# ATMEGA8A.net
KiCad netlist of a schematic drawn in Altium Designer
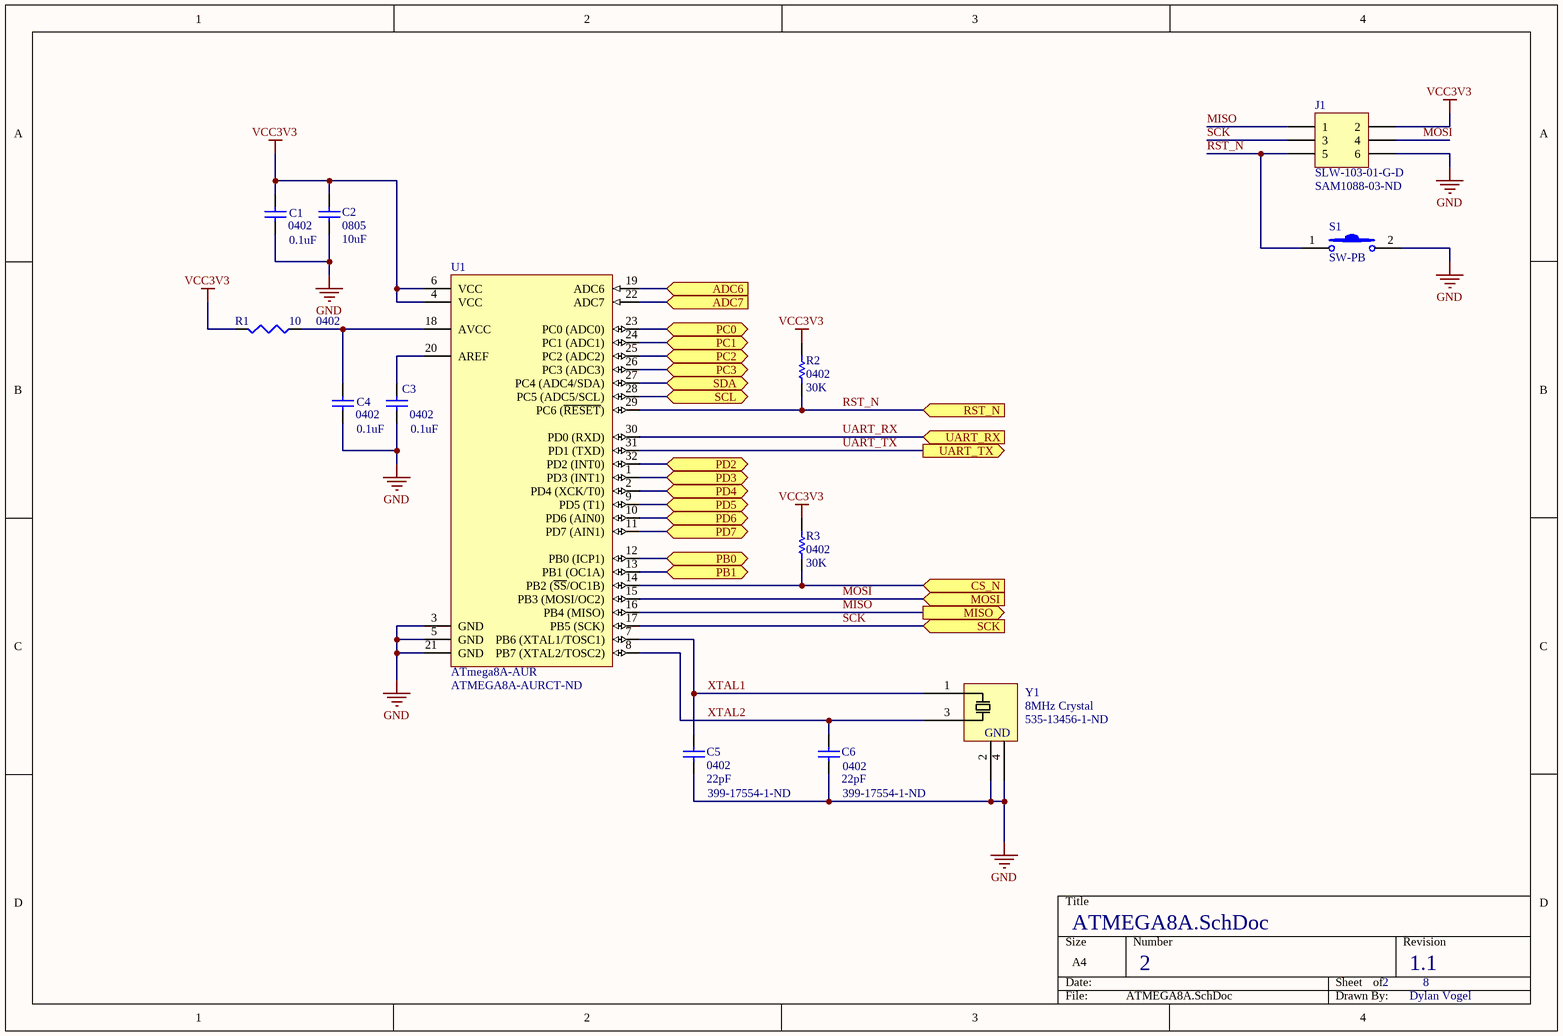
[diagram p0: ATMEGA8A.SchDoc]

(export (version "E")
  (design (tool "Eeschema 10.0.6"))
  (components
    (comp (ref "C1")
      (value "0402")
      (footprint "CAP0402R")
      (description "Capacitor (Semiconductor SIM Model)")
      (fields
        (field (name "ALTIUM_VALUE") "0.1uF")
        (field (name "MANUFACTURER") "Murata")
        (field (name "MANUFACTURER PART NUMBER") "GCM155R71C104KA55J")
        (field (name "PUBLISHER") "Altium Limited")
      )
      (libsource (lib "Miscellaneous Devices") (part "Cap Semi"))
    )
    (comp (ref "C2")
      (value "0805")
      (footprint "CAP0805R")
      (description "Capacitor")
      (fields
        (field (name "ALTIUM_VALUE") "10uF")
        (field (name "MANUFACTURER") "TDK")
        (field (name "MANUFACTURER PART NUMBER") "CGA4J1X7R0J106K125AC")
        (field (name "PUBLISHER") "Altium Limited")
      )
      (libsource (lib "Miscellaneous Devices") (part "Cap"))
    )
    (comp (ref "C3")
      (value "0402")
      (footprint "CAP0402R")
      (description "Capacitor (Semiconductor SIM Model)")
      (fields
        (field (name "ALTIUM_VALUE") "0.1uF")
        (field (name "MANUFACTURER") "Murata")
        (field (name "MANUFACTURER PART NUMBER") "GCM155R71C104KA55J")
        (field (name "PUBLISHER") "Altium Limited")
      )
      (libsource (lib "Miscellaneous Devices") (part "Cap Semi"))
    )
    (comp (ref "C4")
      (value "0402")
      (footprint "CAP0402R")
      (description "Capacitor (Semiconductor SIM Model)")
      (fields
        (field (name "ALTIUM_VALUE") "0.1uF")
        (field (name "MANUFACTURER") "Murata")
        (field (name "MANUFACTURER PART NUMBER") "GCM155R71C104KA55J")
        (field (name "PUBLISHER") "Altium Limited")
      )
      (libsource (lib "Miscellaneous Devices") (part "Cap Semi"))
    )
    (comp (ref "C5")
      (value "0402")
      (footprint "CAP0402R")
      (description "Capacitor")
      (fields
        (field (name "ALTIUM_VALUE") "22pF")
        (field (name "SUPPLIER PART NUMBER 1") "399-17554-1-ND")
        (field (name "MANUFACTURER") "KEMET")
        (field (name "MANUFACTURER PART NUMBER") "C0402C220K4RAC7867")
        (field (name "PUBLISHER") "Altium Limited")
      )
      (libsource (lib "Miscellaneous Devices") (part "Cap"))
    )
    (comp (ref "C6")
      (value "0402")
      (footprint "CAP0402R")
      (description "Capacitor")
      (fields
        (field (name "ALTIUM_VALUE") "22pF")
        (field (name "SUPPLIER PART NUMBER 1") "399-17554-1-ND")
        (field (name "MANUFACTURER") "KEMET")
        (field (name "MANUFACTURER PART NUMBER") "C0402C220K4RAC7867")
        (field (name "PUBLISHER") "Altium Limited")
      )
      (libsource (lib "Miscellaneous Devices") (part "Cap"))
    )
    (comp (ref "J1")
      (value "SLW-103-01-G-D")
      (footprint "SLW-103-01-X-D")
      (fields (field (name "SUPPLIER PART NUMBER 1") "SAM1088-03-ND"))
      (libsource (lib "heron-general") (part "SLW-103-01-G-D"))
    )
    (comp (ref "R1")
      (value "0402")
      (footprint "RES0402R")
      (description "Resistor")
      (fields (field (name "ALTIUM_VALUE") "10") (field (name "PUBLISHER") "Altium Limited"))
      (libsource (lib "Miscellaneous Devices") (part "Res3"))
    )
    (comp (ref "R2")
      (value "0402")
      (footprint "RES0402R")
      (description "Resistor")
      (fields (field (name "ALTIUM_VALUE") "30K") (field (name "PUBLISHER") "Altium Limited"))
      (libsource (lib "Miscellaneous Devices") (part "Res1"))
    )
    (comp (ref "R3")
      (value "0402")
      (footprint "RES0402R")
      (description "Resistor")
      (fields (field (name "ALTIUM_VALUE") "30K") (field (name "PUBLISHER") "Altium Limited"))
      (libsource (lib "Miscellaneous Devices") (part "Res1"))
    )
    (comp (ref "S1")
      (value "SW-PB")
      (footprint "PTS830GM140 SMTR LFS - Pushbutton")
      (description "Schematic symbol for a generic 2-pin pushbutton, OFF-mom.")
      (libsource (lib "heron-general") (part "Pushbutton - Low Profile"))
    )
    (comp (ref "U1")
      (value "ATmega8A-AUR")
      (footprint "QFP80P900X900X120-32")
      (fields
        (field (name "PARTNUMBER") "ATMEGA8A-AUR")
        (field (name "SUPPLIER PART NUMBER 1") "ATMEGA8A-AURCT-ND")
      )
      (libsource (lib "heron-general") (part "ATMEGA8A-AUR"))
    )
    (comp (ref "Y1")
      (value "8MHz Crystal")
      (footprint "OSCSC500X320X110-4N")
      (description "8MHz Abracom 4-pin crystal.")
      (fields (field (name "SUPPLIER PART NUMBER 1") "535-13456-1-ND"))
      (libsource (lib "heron-general") (part "AMB3B-8MHz"))
    )
  )
  (nets
    (net (code "1") (name "/ADC6") (class "Default")
      (node (ref "U1") (pin "19") (pinfunction "ADC6_19") (pintype "input"))
    )
    (net (code "2") (name "/ADC7") (class "Default")
      (node (ref "U1") (pin "22") (pinfunction "ADC7_22") (pintype "input"))
    )
    (net (code "3") (name "/CS_N") (class "Default")
      (node (ref "R3") (pin "1") (pinfunction "1_1") (pintype "passive"))
      (node (ref "U1") (pin "14") (pinfunction "PB2_(~{SS}/OC1B)_14") (pintype "bidirectional"))
    )
    (net (code "4") (name "/MISO") (class "Default")
      (node (ref "J1") (pin "1") (pinfunction "1_1") (pintype "passive"))
      (node (ref "U1") (pin "16") (pinfunction "PB4_(MISO)_16") (pintype "bidirectional"))
    )
    (net (code "5") (name "/MOSI") (class "Default")
      (node (ref "J1") (pin "4") (pinfunction "4_4") (pintype "passive"))
      (node (ref "U1") (pin "15") (pinfunction "PB3_(MOSI/OC2)_15") (pintype "bidirectional"))
    )
    (net (code "6") (name "/PB0") (class "Default")
      (node (ref "U1") (pin "12") (pinfunction "PB0_(ICP1)_12") (pintype "bidirectional"))
    )
    (net (code "7") (name "/PB1") (class "Default")
      (node (ref "U1") (pin "13") (pinfunction "PB1_(OC1A)_13") (pintype "bidirectional"))
    )
    (net (code "8") (name "/PC0") (class "Default")
      (node (ref "U1") (pin "23") (pinfunction "PC0_(ADC0)_23") (pintype "bidirectional"))
    )
    (net (code "9") (name "/PC1") (class "Default")
      (node (ref "U1") (pin "24") (pinfunction "PC1_(ADC1)_24") (pintype "bidirectional"))
    )
    (net (code "10") (name "/PC2") (class "Default")
      (node (ref "U1") (pin "25") (pinfunction "PC2_(ADC2)_25") (pintype "bidirectional"))
    )
    (net (code "11") (name "/PC3") (class "Default")
      (node (ref "U1") (pin "26") (pinfunction "PC3_(ADC3)_26") (pintype "bidirectional"))
    )
    (net (code "12") (name "/PD2") (class "Default")
      (node (ref "U1") (pin "32") (pinfunction "PD2_(INT0)_32") (pintype "bidirectional"))
    )
    (net (code "13") (name "/PD3") (class "Default")
      (node (ref "U1") (pin "1") (pinfunction "PD3_(INT1)_1") (pintype "bidirectional"))
    )
    (net (code "14") (name "/PD4") (class "Default")
      (node (ref "U1") (pin "2") (pinfunction "PD4_(XCK/T0)_2") (pintype "bidirectional"))
    )
    (net (code "15") (name "/PD5") (class "Default")
      (node (ref "U1") (pin "9") (pinfunction "PD5_(T1)_9") (pintype "bidirectional"))
    )
    (net (code "16") (name "/PD6") (class "Default")
      (node (ref "U1") (pin "10") (pinfunction "PD6_(AIN0)_10") (pintype "bidirectional"))
    )
    (net (code "17") (name "/PD7") (class "Default")
      (node (ref "U1") (pin "11") (pinfunction "PD7_(AIN1)_11") (pintype "bidirectional"))
    )
    (net (code "18") (name "/RST_N") (class "Default")
      (node (ref "J1") (pin "5") (pinfunction "5_5") (pintype "passive"))
      (node (ref "R2") (pin "1") (pinfunction "1_1") (pintype "passive"))
      (node (ref "S1") (pin "1") (pinfunction "1_1") (pintype "passive"))
      (node (ref "U1") (pin "29") (pinfunction "PC6_(~{RESET})_29") (pintype "bidirectional"))
    )
    (net (code "19") (name "/SCK") (class "Default")
      (node (ref "J1") (pin "3") (pinfunction "3_3") (pintype "passive"))
      (node (ref "U1") (pin "17") (pinfunction "PB5_(SCK)_17") (pintype "bidirectional"))
    )
    (net (code "20") (name "/SCL") (class "Default")
      (node (ref "U1") (pin "28") (pinfunction "PC5_(ADC5/SCL)_28") (pintype "bidirectional"))
    )
    (net (code "21") (name "/SDA") (class "Default")
      (node (ref "U1") (pin "27") (pinfunction "PC4_(ADC4/SDA)_27") (pintype "bidirectional"))
    )
    (net (code "22") (name "/UART_RX") (class "Default")
      (node (ref "U1") (pin "30") (pinfunction "PD0_(RXD)_30") (pintype "bidirectional"))
    )
    (net (code "23") (name "/UART_TX") (class "Default")
      (node (ref "U1") (pin "31") (pinfunction "PD1_(TXD)_31") (pintype "bidirectional"))
    )
    (net (code "24") (name "/XTAL1") (class "Default")
      (node (ref "C5") (pin "2") (pinfunction "2_2") (pintype "passive"))
      (node (ref "U1") (pin "7") (pinfunction "PB6_(XTAL1/TOSC1)_7") (pintype "bidirectional"))
      (node (ref "Y1") (pin "1") (pinfunction "IN_1") (pintype "passive"))
    )
    (net (code "25") (name "/XTAL2") (class "Default")
      (node (ref "C6") (pin "2") (pinfunction "2_2") (pintype "passive"))
      (node (ref "U1") (pin "8") (pinfunction "PB7_(XTAL2/TOSC2)_8") (pintype "bidirectional"))
      (node (ref "Y1") (pin "3") (pinfunction "IN_3") (pintype "passive"))
    )
    (net (code "26") (name "GND") (class "Default")
      (node (ref "C1") (pin "1") (pinfunction "1_1") (pintype "passive"))
      (node (ref "C2") (pin "1") (pinfunction "1_1") (pintype "passive"))
      (node (ref "C3") (pin "1") (pinfunction "1_1") (pintype "passive"))
      (node (ref "C4") (pin "1") (pinfunction "1_1") (pintype "passive"))
      (node (ref "C5") (pin "1") (pinfunction "1_1") (pintype "passive"))
      (node (ref "C6") (pin "1") (pinfunction "1_1") (pintype "passive"))
      (node (ref "J1") (pin "6") (pinfunction "6_6") (pintype "passive"))
      (node (ref "S1") (pin "2") (pinfunction "2_2") (pintype "passive"))
      (node (ref "U1") (pin "21") (pinfunction "GND_21") (pintype "power_in"))
      (node (ref "U1") (pin "3") (pinfunction "GND_3") (pintype "power_in"))
      (node (ref "U1") (pin "5") (pinfunction "GND_5") (pintype "power_in"))
      (node (ref "Y1") (pin "2") (pinfunction "5_2") (pintype "passive"))
      (node (ref "Y1") (pin "4") (pinfunction "4_4") (pintype "passive"))
    )
    (net (code "27") (name "Net-(U1-AREF)") (class "Default")
      (node (ref "C3") (pin "2") (pinfunction "2_2") (pintype "passive"))
      (node (ref "U1") (pin "20") (pinfunction "AREF_20") (pintype "power_in"))
    )
    (net (code "28") (name "Net-(U1-AVCC)") (class "Default")
      (node (ref "C4") (pin "2") (pinfunction "2_2") (pintype "passive"))
      (node (ref "R1") (pin "1") (pinfunction "1_1") (pintype "passive"))
      (node (ref "U1") (pin "18") (pinfunction "AVCC_18") (pintype "power_in"))
    )
    (net (code "29") (name "VCC3V3") (class "Default")
      (node (ref "C1") (pin "2") (pinfunction "2_2") (pintype "passive"))
      (node (ref "C2") (pin "2") (pinfunction "2_2") (pintype "passive"))
      (node (ref "J1") (pin "2") (pinfunction "2_2") (pintype "passive"))
      (node (ref "R1") (pin "2") (pinfunction "2_2") (pintype "passive"))
      (node (ref "R2") (pin "2") (pinfunction "2_2") (pintype "passive"))
      (node (ref "R3") (pin "2") (pinfunction "2_2") (pintype "passive"))
      (node (ref "U1") (pin "4") (pinfunction "VCC_4") (pintype "power_in"))
      (node (ref "U1") (pin "6") (pinfunction "VCC_6") (pintype "power_in"))
    )
  )
)
